# XstractiK_Domination_Player_Forearm_V1.net
KiCad netlist of a schematic drawn in EAGLE
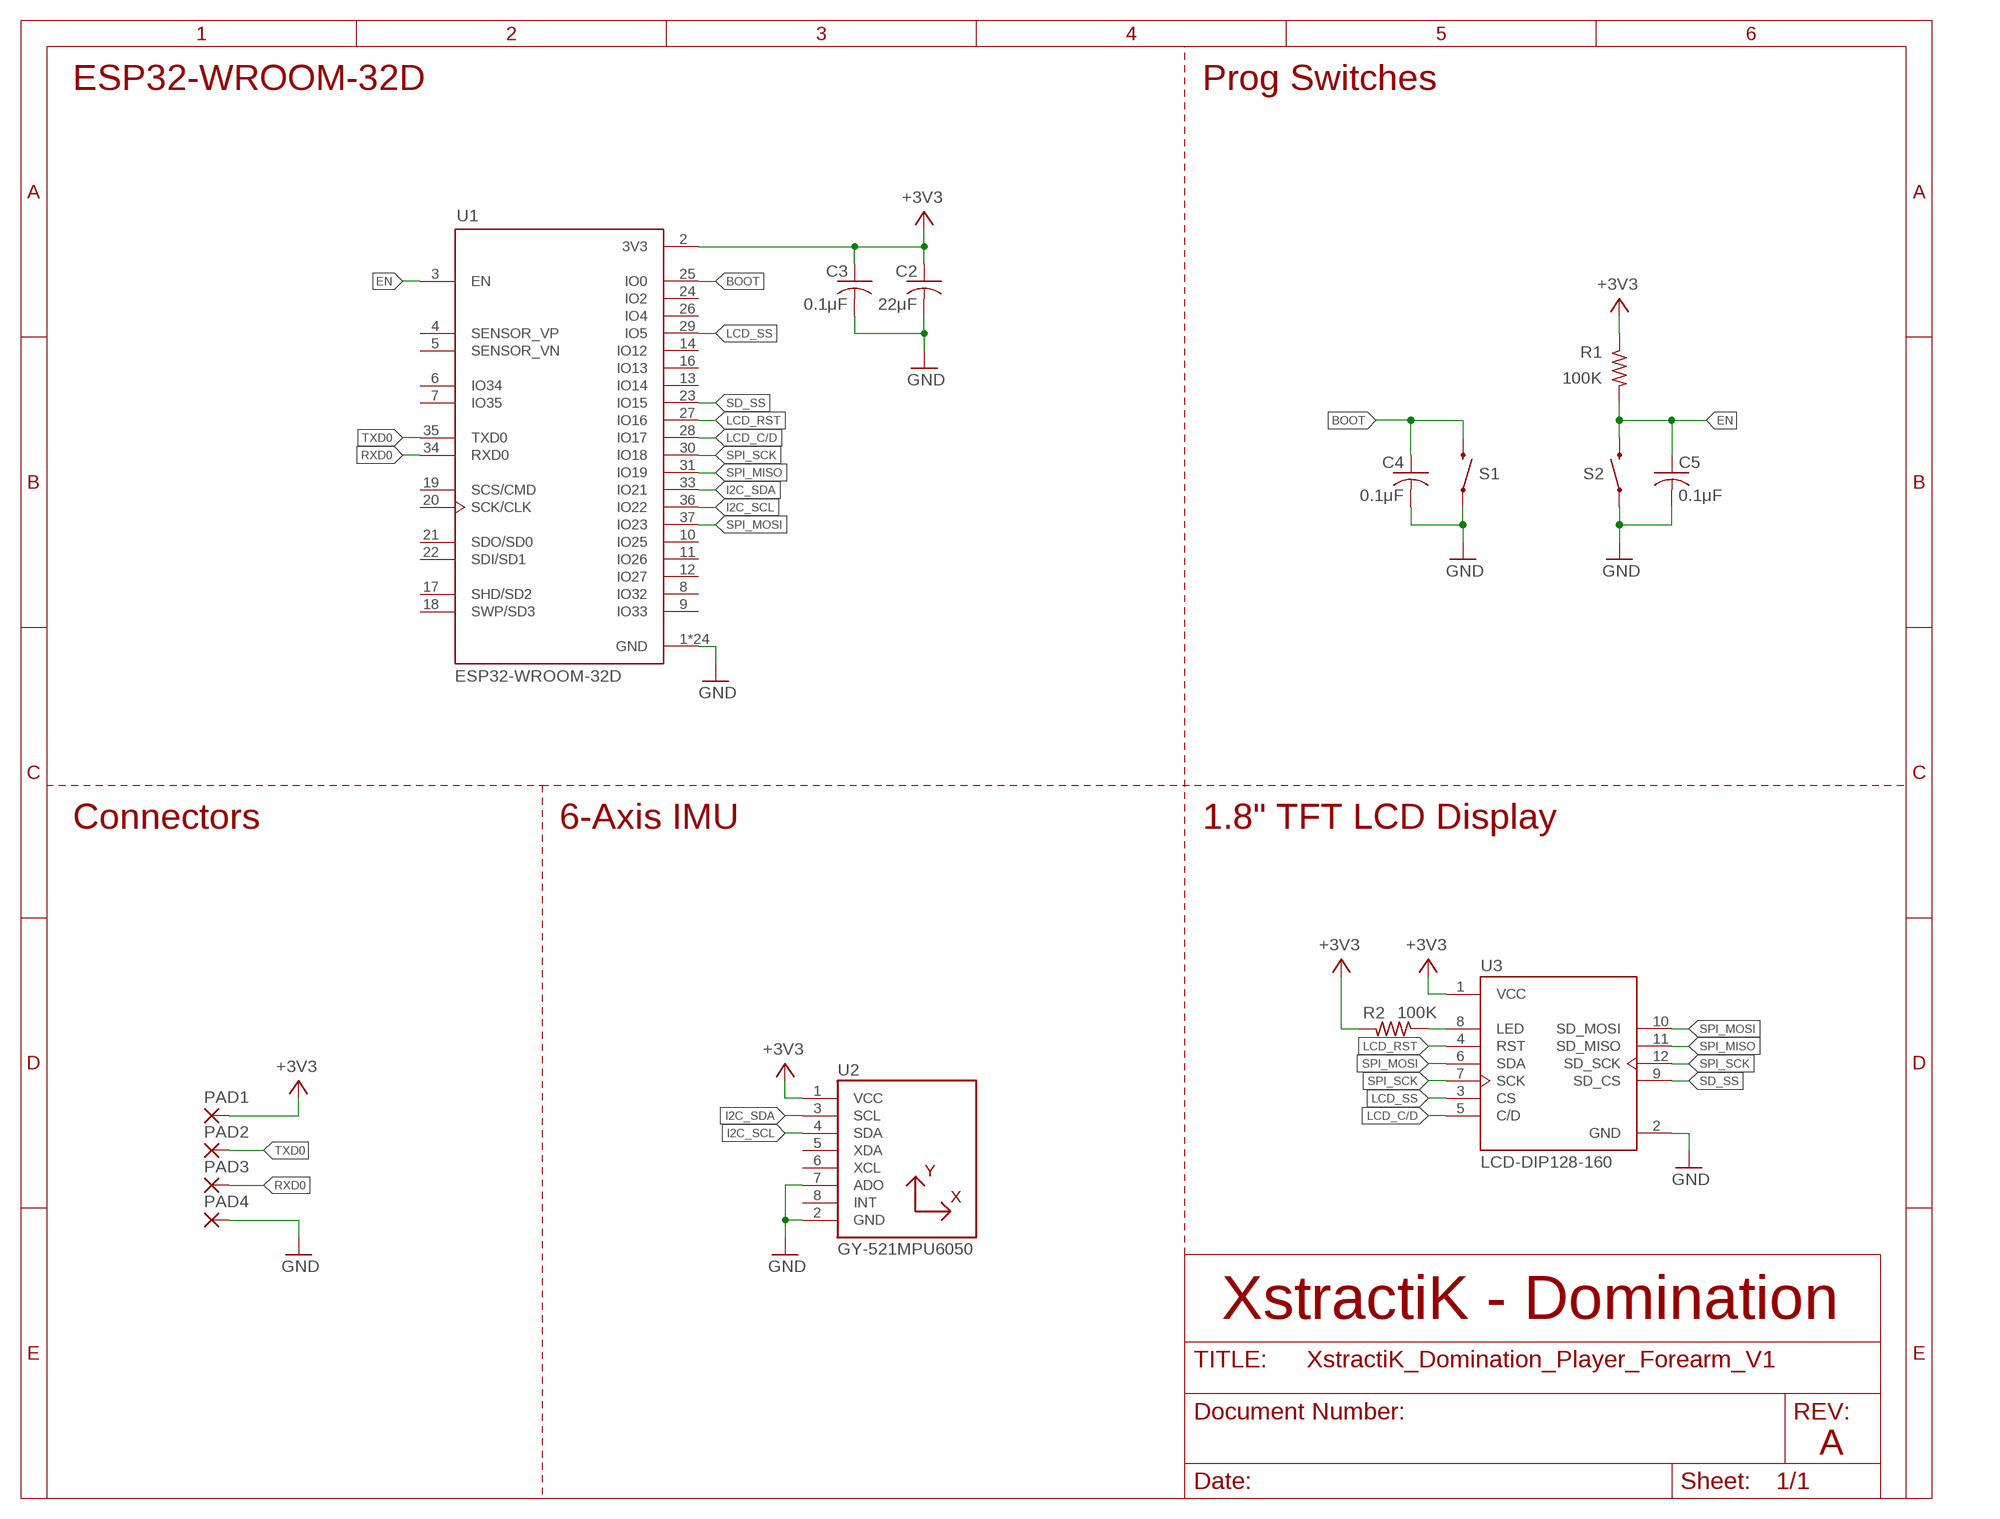
[diagram p0: schematic, sheet 1]

(export (version "E")
  (design (tool "Eeschema 10.0.6"))
  (components
    (comp (ref "C2")
      (value "22μF")
      (footprint "eagle-import:C0805")
      (libsource (lib "eagle-import") (part "C-USC0805"))
    )
    (comp (ref "C3")
      (value "0.1μF")
      (footprint "eagle-import:C0805")
      (libsource (lib "eagle-import") (part "C-USC0805"))
    )
    (comp (ref "C4")
      (value "0.1μF")
      (footprint "eagle-import:C0805")
      (libsource (lib "eagle-import") (part "C-USC0805"))
    )
    (comp (ref "C5")
      (value "0.1μF")
      (footprint "eagle-import:C0805")
      (libsource (lib "eagle-import") (part "C-USC0805"))
    )
    (comp (ref "PAD1")
      (value "WIREPADSMD5-1,8")
      (footprint "eagle-import:5-1,8")
      (libsource (lib "eagle-import") (part "WIREPADSMD5-1,8"))
    )
    (comp (ref "PAD2")
      (value "WIREPADSMD5-1,8")
      (footprint "eagle-import:5-1,8")
      (libsource (lib "eagle-import") (part "WIREPADSMD5-1,8"))
    )
    (comp (ref "PAD3")
      (value "WIREPADSMD5-1,8")
      (footprint "eagle-import:5-1,8")
      (libsource (lib "eagle-import") (part "WIREPADSMD5-1,8"))
    )
    (comp (ref "PAD4")
      (value "WIREPADSMD5-1,8")
      (footprint "eagle-import:5-1,8")
      (libsource (lib "eagle-import") (part "WIREPADSMD5-1,8"))
    )
    (comp (ref "R1")
      (value "100K")
      (footprint "eagle-import:R0805")
      (libsource (lib "eagle-import") (part "R-US_R0805"))
    )
    (comp (ref "R2")
      (value "100K")
      (footprint "eagle-import:R0805")
      (libsource (lib "eagle-import") (part "R-US_R0805"))
    )
    (comp (ref "S1")
      (value "MOMENTARY-SWITCH-SPST-SMD-5.2MM-TALL")
      (footprint "eagle-import:TACTILE_SWITCH_SMD_5.2MM")
      (libsource (lib "eagle-import") (part "MOMENTARY-SWITCH-SPST-SMD-5.2MM-TALL"))
    )
    (comp (ref "S2")
      (value "MOMENTARY-SWITCH-SPST-SMD-5.2MM-TALL")
      (footprint "eagle-import:TACTILE_SWITCH_SMD_5.2MM")
      (libsource (lib "eagle-import") (part "MOMENTARY-SWITCH-SPST-SMD-5.2MM-TALL"))
    )
    (comp (ref "U1")
      (value "ESP32-WROOM-32D")
      (footprint "eagle-import:MODULE_ESP32-WROOM-32D")
      (fields (field (name "MF") "Espressif Systems"))
      (libsource (lib "eagle-import") (part "ESP32-WROOM-32D"))
    )
    (comp (ref "U2")
      (value "GY-521MPU6050")
      (footprint "eagle-import:GY-521")
      (fields (field (name "MF") "GODREAM FORDREAM CO., LIMITED") (field (name "MP") "GY-521"))
      (libsource (lib "eagle-import") (part "GY-521MPU6050"))
    )
    (comp (ref "U3")
      (value "LCD-DIP128-160")
      (footprint "eagle-import:LCD-DIP128-160")
      (libsource (lib "eagle-import") (part "LCD-DIP128-160"))
    )
  )
  (nets
    (net (code "1") (name "+3V3") (class "Default")
      (node (ref "C2") (pin "1") (pinfunction "1_1") (pintype "passive"))
      (node (ref "C3") (pin "1") (pinfunction "1_1") (pintype "passive"))
      (node (ref "PAD1") (pin "1") (pinfunction "P_1") (pintype "passive"))
      (node (ref "R1") (pin "1") (pinfunction "1_1") (pintype "passive"))
      (node (ref "R2") (pin "2") (pinfunction "2_2") (pintype "passive"))
      (node (ref "U1") (pin "2") (pinfunction "3V3_2") (pintype "power_in"))
      (node (ref "U2") (pin "1") (pinfunction "VCC_1") (pintype "power_in"))
      (node (ref "U3") (pin "1") (pinfunction "VCC_1") (pintype "power_in"))
    )
    (net (code "2") (name "BOOT") (class "Default")
      (node (ref "C4") (pin "1") (pinfunction "1_1") (pintype "passive"))
      (node (ref "S1") (pin "3") (pinfunction "2_3") (pintype "passive"))
      (node (ref "U1") (pin "25") (pinfunction "IO0_25") (pintype "bidirectional"))
    )
    (net (code "3") (name "EN") (class "Default")
      (node (ref "C5") (pin "1") (pinfunction "1_1") (pintype "passive"))
      (node (ref "R1") (pin "2") (pinfunction "2_2") (pintype "passive"))
      (node (ref "S2") (pin "3") (pinfunction "2_3") (pintype "passive"))
      (node (ref "U1") (pin "3") (pinfunction "EN_3") (pintype "input"))
    )
    (net (code "4") (name "GND") (class "Default")
      (node (ref "C2") (pin "2") (pinfunction "2_2") (pintype "passive"))
      (node (ref "C3") (pin "2") (pinfunction "2_2") (pintype "passive"))
      (node (ref "C4") (pin "2") (pinfunction "2_2") (pintype "passive"))
      (node (ref "C5") (pin "2") (pinfunction "2_2") (pintype "passive"))
      (node (ref "PAD4") (pin "1") (pinfunction "P_1") (pintype "passive"))
      (node (ref "S1") (pin "1") (pinfunction "1_1") (pintype "passive"))
      (node (ref "S2") (pin "1") (pinfunction "1_1") (pintype "passive"))
      (node (ref "U1") (pin "1") (pinfunction "GND_1") (pintype "power_in"))
      (node (ref "U1") (pin "15") (pinfunction "GND_15") (pintype "power_in"))
      (node (ref "U1") (pin "38") (pinfunction "GND_38") (pintype "power_in"))
      (node (ref "U1") (pin "39_1") (pinfunction "GND_39_1") (pintype "power_in"))
      (node (ref "U1") (pin "39_10") (pinfunction "GND_39_10") (pintype "power_in"))
      (node (ref "U1") (pin "39_11") (pinfunction "GND_39_11") (pintype "power_in"))
      (node (ref "U1") (pin "39_12") (pinfunction "GND_39_12") (pintype "power_in"))
      (node (ref "U1") (pin "39_13") (pinfunction "GND_39_13") (pintype "power_in"))
      (node (ref "U1") (pin "39_14") (pinfunction "GND_39_14") (pintype "power_in"))
      (node (ref "U1") (pin "39_15") (pinfunction "GND_39_15") (pintype "power_in"))
      (node (ref "U1") (pin "39_16") (pinfunction "GND_39_16") (pintype "power_in"))
      (node (ref "U1") (pin "39_17") (pinfunction "GND_39_17") (pintype "power_in"))
      (node (ref "U1") (pin "39_18") (pinfunction "GND_39_18") (pintype "power_in"))
      (node (ref "U1") (pin "39_19") (pinfunction "GND_39_19") (pintype "power_in"))
      (node (ref "U1") (pin "39_2") (pinfunction "GND_39_2") (pintype "power_in"))
      (node (ref "U1") (pin "39_20") (pinfunction "GND_39_20") (pintype "power_in"))
      (node (ref "U1") (pin "39_21") (pinfunction "GND_39_21") (pintype "power_in"))
      (node (ref "U1") (pin "39_3") (pinfunction "GND_39_3") (pintype "power_in"))
      (node (ref "U1") (pin "39_4") (pinfunction "GND_39_4") (pintype "power_in"))
      (node (ref "U1") (pin "39_5") (pinfunction "GND_39_5") (pintype "power_in"))
      (node (ref "U1") (pin "39_6") (pinfunction "GND_39_6") (pintype "power_in"))
      (node (ref "U1") (pin "39_7") (pinfunction "GND_39_7") (pintype "power_in"))
      (node (ref "U1") (pin "39_8") (pinfunction "GND_39_8") (pintype "power_in"))
      (node (ref "U1") (pin "39_9") (pinfunction "GND_39_9") (pintype "power_in"))
      (node (ref "U2") (pin "2") (pinfunction "GND_2") (pintype "power_in"))
      (node (ref "U2") (pin "7") (pinfunction "ADO_7") (pintype "input"))
      (node (ref "U3") (pin "2") (pinfunction "GND_2") (pintype "power_in"))
    )
    (net (code "5") (name "I2C_SCL") (class "Default")
      (node (ref "U1") (pin "36") (pinfunction "IO22_36") (pintype "bidirectional"))
      (node (ref "U2") (pin "4") (pinfunction "SDA_4") (pintype "bidirectional"))
    )
    (net (code "6") (name "I2C_SDA") (class "Default")
      (node (ref "U1") (pin "33") (pinfunction "IO21_33") (pintype "bidirectional"))
      (node (ref "U2") (pin "3") (pinfunction "SCL_3") (pintype "output"))
    )
    (net (code "7") (name "LCD_C{slash}D") (class "Default")
      (node (ref "U1") (pin "28") (pinfunction "IO17_28") (pintype "bidirectional"))
      (node (ref "U3") (pin "5") (pinfunction "C/D_5") (pintype "input"))
    )
    (net (code "8") (name "LCD_RST") (class "Default")
      (node (ref "U1") (pin "27") (pinfunction "IO16_27") (pintype "bidirectional"))
      (node (ref "U3") (pin "4") (pinfunction "RST_4") (pintype "input"))
    )
    (net (code "9") (name "LCD_SS") (class "Default")
      (node (ref "U1") (pin "29") (pinfunction "IO5_29") (pintype "bidirectional"))
      (node (ref "U3") (pin "3") (pinfunction "CS_3") (pintype "input"))
    )
    (net (code "10") (name "Net-(U3-LED)") (class "Default")
      (node (ref "R2") (pin "1") (pinfunction "1_1") (pintype "passive"))
      (node (ref "U3") (pin "8") (pinfunction "LED_8") (pintype "input"))
    )
    (net (code "11") (name "RXD0") (class "Default")
      (node (ref "PAD3") (pin "1") (pinfunction "P_1") (pintype "passive"))
      (node (ref "U1") (pin "34") (pinfunction "RXD0_34") (pintype "bidirectional"))
    )
    (net (code "12") (name "SD_SS") (class "Default")
      (node (ref "U1") (pin "23") (pinfunction "IO15_23") (pintype "bidirectional"))
      (node (ref "U3") (pin "9") (pinfunction "SD_CS_9") (pintype "input"))
    )
    (net (code "13") (name "SPI_MISO") (class "Default")
      (node (ref "U1") (pin "31") (pinfunction "IO19_31") (pintype "bidirectional"))
      (node (ref "U3") (pin "11") (pinfunction "SD_MISO_11") (pintype "bidirectional"))
    )
    (net (code "14") (name "SPI_MOSI") (class "Default")
      (node (ref "U1") (pin "37") (pinfunction "IO23_37") (pintype "bidirectional"))
      (node (ref "U3") (pin "10") (pinfunction "SD_MOSI_10") (pintype "bidirectional"))
      (node (ref "U3") (pin "6") (pinfunction "SDA_6") (pintype "bidirectional"))
    )
    (net (code "15") (name "SPI_SCK") (class "Default")
      (node (ref "U1") (pin "30") (pinfunction "IO18_30") (pintype "bidirectional"))
      (node (ref "U3") (pin "12") (pinfunction "SD_SCK_12") (pintype "bidirectional"))
      (node (ref "U3") (pin "7") (pinfunction "SCK_7") (pintype "bidirectional"))
    )
    (net (code "16") (name "TXD0") (class "Default")
      (node (ref "PAD2") (pin "1") (pinfunction "P_1") (pintype "passive"))
      (node (ref "U1") (pin "35") (pinfunction "TXD0_35") (pintype "bidirectional"))
    )
    (net (code "17") (name "unconnected-(U1-IO2-Pad24)") (class "Default")
      (node (ref "U1") (pin "24") (pinfunction "IO2_24") (pintype "bidirectional"))
    )
    (net (code "18") (name "unconnected-(U1-IO4-Pad26)") (class "Default")
      (node (ref "U1") (pin "26") (pinfunction "IO4_26") (pintype "bidirectional"))
    )
    (net (code "19") (name "unconnected-(U1-IO12-Pad14)") (class "Default")
      (node (ref "U1") (pin "14") (pinfunction "IO12_14") (pintype "bidirectional"))
    )
    (net (code "20") (name "unconnected-(U1-IO13-Pad16)") (class "Default")
      (node (ref "U1") (pin "16") (pinfunction "IO13_16") (pintype "bidirectional"))
    )
    (net (code "21") (name "unconnected-(U1-IO14-Pad13)") (class "Default")
      (node (ref "U1") (pin "13") (pinfunction "IO14_13") (pintype "bidirectional"))
    )
    (net (code "22") (name "unconnected-(U1-IO25-Pad10)") (class "Default")
      (node (ref "U1") (pin "10") (pinfunction "IO25_10") (pintype "bidirectional"))
    )
    (net (code "23") (name "unconnected-(U1-IO26-Pad11)") (class "Default")
      (node (ref "U1") (pin "11") (pinfunction "IO26_11") (pintype "bidirectional"))
    )
    (net (code "24") (name "unconnected-(U1-IO27-Pad12)") (class "Default")
      (node (ref "U1") (pin "12") (pinfunction "IO27_12") (pintype "bidirectional"))
    )
    (net (code "25") (name "unconnected-(U1-IO32-Pad8)") (class "Default")
      (node (ref "U1") (pin "8") (pinfunction "IO32_8") (pintype "bidirectional"))
    )
    (net (code "26") (name "unconnected-(U1-IO33-Pad9)") (class "Default")
      (node (ref "U1") (pin "9") (pinfunction "IO33_9") (pintype "bidirectional"))
    )
    (net (code "27") (name "unconnected-(U1-IO34-Pad6)") (class "Default")
      (node (ref "U1") (pin "6") (pinfunction "IO34_6") (pintype "input"))
    )
    (net (code "28") (name "unconnected-(U1-IO35-Pad7)") (class "Default")
      (node (ref "U1") (pin "7") (pinfunction "IO35_7") (pintype "input"))
    )
    (net (code "29") (name "unconnected-(U1-SCK{slash}CLK-Pad20)") (class "Default")
      (node (ref "U1") (pin "20") (pinfunction "SCK/CLK_20") (pintype "bidirectional"))
    )
    (net (code "30") (name "unconnected-(U1-SCS{slash}CMD-Pad19)") (class "Default")
      (node (ref "U1") (pin "19") (pinfunction "SCS/CMD_19") (pintype "bidirectional"))
    )
    (net (code "31") (name "unconnected-(U1-SDI{slash}SD1-Pad22)") (class "Default")
      (node (ref "U1") (pin "22") (pinfunction "SDI/SD1_22") (pintype "bidirectional"))
    )
    (net (code "32") (name "unconnected-(U1-SDO{slash}SD0-Pad21)") (class "Default")
      (node (ref "U1") (pin "21") (pinfunction "SDO/SD0_21") (pintype "bidirectional"))
    )
    (net (code "33") (name "unconnected-(U1-SENSOR_VN-Pad5)") (class "Default")
      (node (ref "U1") (pin "5") (pinfunction "SENSOR_VN_5") (pintype "input"))
    )
    (net (code "34") (name "unconnected-(U1-SENSOR_VP-Pad4)") (class "Default")
      (node (ref "U1") (pin "4") (pinfunction "SENSOR_VP_4") (pintype "input"))
    )
    (net (code "35") (name "unconnected-(U1-SHD{slash}SD2-Pad17)") (class "Default")
      (node (ref "U1") (pin "17") (pinfunction "SHD/SD2_17") (pintype "bidirectional"))
    )
    (net (code "36") (name "unconnected-(U1-SWP{slash}SD3-Pad18)") (class "Default")
      (node (ref "U1") (pin "18") (pinfunction "SWP/SD3_18") (pintype "bidirectional"))
    )
    (net (code "37") (name "unconnected-(U2-INT-Pad8)") (class "Default")
      (node (ref "U2") (pin "8") (pinfunction "INT_8") (pintype "output"))
    )
    (net (code "38") (name "unconnected-(U2-XCL-Pad6)") (class "Default")
      (node (ref "U2") (pin "6") (pinfunction "XCL_6") (pintype "bidirectional"))
    )
    (net (code "39") (name "unconnected-(U2-XDA-Pad5)") (class "Default")
      (node (ref "U2") (pin "5") (pinfunction "XDA_5") (pintype "bidirectional"))
    )
  )
)
